# MCU_STM32F407.net
KiCad netlist of a schematic drawn in Altium Designer
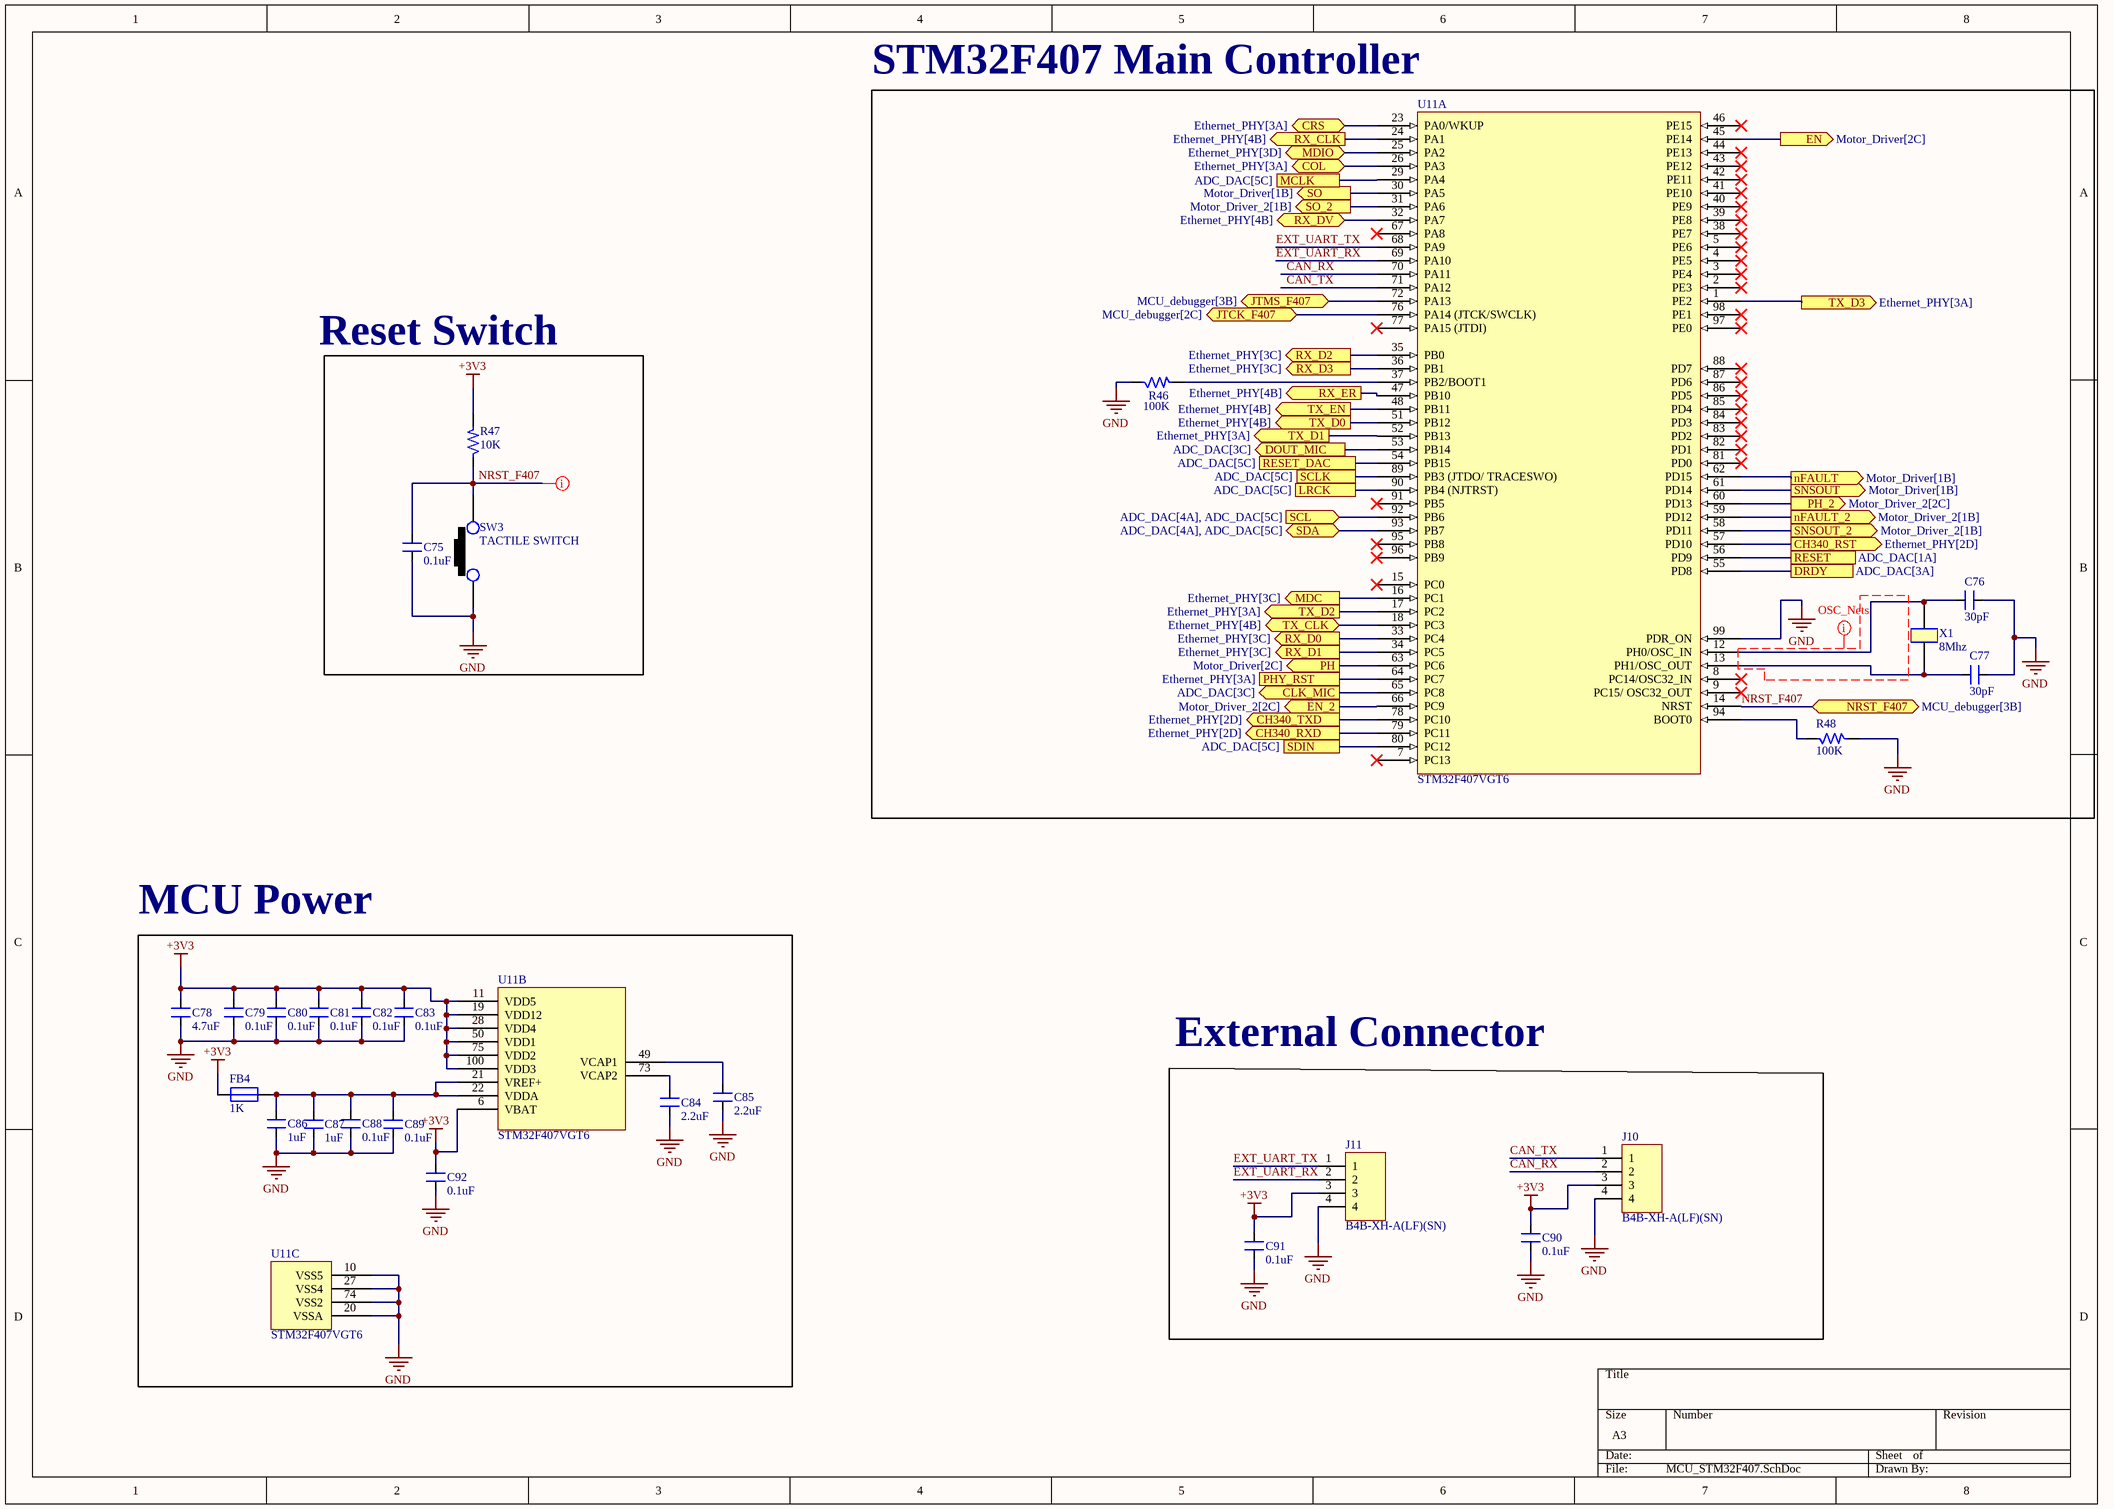
[diagram p0: MCU_STM32F407.SchDoc]

(export (version "E")
  (design (tool "Eeschema 10.0.6"))
  (components
    (comp (ref "C75")
      (value "0.1uF")
      (footprint "CAP_0805")
      (description "0.1µF ±10% 50V Ceramic Capacitor X7R 0805 (2012 Metric)")
      (fields
        (field (name "MANUFACTURER") "Samsung")
        (field (name "MANUFACTURER PART NUMBER") "CL21B104KBCNNNC")
      )
      (libsource (lib "STM32F407_Board") (part "CAP_0.1uF-50V-10%-0805"))
    )
    (comp (ref "C76")
      (value "30pF")
      (footprint "CAP_0805")
      (description "±10% 50V Ceramic Capacitor C0G, NP0 0805 (2012 Metric)")
      (fields
        (field (name "MANUFACTURER PART NUMBER") "C0805C300K5GAC7800")
        (field (name "MANUFACTURER") "KEMET")
      )
      (libsource (lib "STM32F407_Board") (part "CAP_30pF-50V-10%-0805"))
    )
    (comp (ref "C77")
      (value "30pF")
      (footprint "CAP_0805")
      (description "±10% 50V Ceramic Capacitor C0G, NP0 0805 (2012 Metric)")
      (fields
        (field (name "MANUFACTURER PART NUMBER") "C0805C300K5GAC7800")
        (field (name "MANUFACTURER") "KEMET")
      )
      (libsource (lib "STM32F407_Board") (part "CAP_30pF-50V-10%-0805"))
    )
    (comp (ref "C78")
      (value "4.7uF")
      (footprint "CAP_0805")
      (description "4.7µF ±10% 50V Ceramic Capacitor X5R 0805 (2012 Metric)")
      (fields
        (field (name "MANUFACTURER") "Yageo")
        (field (name "MANUFACTURER PART NUMBER") "GRM21BR61H475KE51L")
      )
      (libsource (lib "STM32F407_Board") (part "CAP_4.7uF-50V-10%-0805"))
    )
    (comp (ref "C79")
      (value "0.1uF")
      (footprint "CAP_0805")
      (description "0.1µF ±10% 50V Ceramic Capacitor X7R 0805 (2012 Metric)")
      (fields
        (field (name "MANUFACTURER") "Samsung")
        (field (name "MANUFACTURER PART NUMBER") "CL21B104KBCNNNC")
      )
      (libsource (lib "STM32F407_Board") (part "CAP_0.1uF-50V-10%-0805"))
    )
    (comp (ref "C80")
      (value "0.1uF")
      (footprint "CAP_0805")
      (description "0.1µF ±10% 50V Ceramic Capacitor X7R 0805 (2012 Metric)")
      (fields
        (field (name "MANUFACTURER") "Samsung")
        (field (name "MANUFACTURER PART NUMBER") "CL21B104KBCNNNC")
      )
      (libsource (lib "STM32F407_Board") (part "CAP_0.1uF-50V-10%-0805"))
    )
    (comp (ref "C81")
      (value "0.1uF")
      (footprint "CAP_0805")
      (description "0.1µF ±10% 50V Ceramic Capacitor X7R 0805 (2012 Metric)")
      (fields
        (field (name "MANUFACTURER") "Samsung")
        (field (name "MANUFACTURER PART NUMBER") "CL21B104KBCNNNC")
      )
      (libsource (lib "STM32F407_Board") (part "CAP_0.1uF-50V-10%-0805"))
    )
    (comp (ref "C82")
      (value "0.1uF")
      (footprint "CAP_0805")
      (description "0.1µF ±10% 50V Ceramic Capacitor X7R 0805 (2012 Metric)")
      (fields
        (field (name "MANUFACTURER") "Samsung")
        (field (name "MANUFACTURER PART NUMBER") "CL21B104KBCNNNC")
      )
      (libsource (lib "STM32F407_Board") (part "CAP_0.1uF-50V-10%-0805"))
    )
    (comp (ref "C83")
      (value "0.1uF")
      (footprint "CAP_0805")
      (description "0.1µF ±10% 50V Ceramic Capacitor X7R 0805 (2012 Metric)")
      (fields
        (field (name "MANUFACTURER") "Samsung")
        (field (name "MANUFACTURER PART NUMBER") "CL21B104KBCNNNC")
      )
      (libsource (lib "STM32F407_Board") (part "CAP_0.1uF-50V-10%-0805"))
    )
    (comp (ref "C84")
      (value "2.2uF")
      (footprint "CAP_0805")
      (description "2.2µF ±10% 25V Ceramic Capacitor X7R 0805 (2012 Metric)")
      (fields
        (field (name "MANUFACTURER") "KEMET")
        (field (name "MANUFACTURER PART NUMBER") "CL21B225KAFNFNE")
      )
      (libsource (lib "STM32F407_Board") (part "CAP_2.2uF-25V-10%-0805"))
    )
    (comp (ref "C85")
      (value "2.2uF")
      (footprint "CAP_0805")
      (description "2.2µF ±10% 25V Ceramic Capacitor X7R 0805 (2012 Metric)")
      (fields
        (field (name "MANUFACTURER") "KEMET")
        (field (name "MANUFACTURER PART NUMBER") "CL21B225KAFNFNE")
      )
      (libsource (lib "STM32F407_Board") (part "CAP_2.2uF-25V-10%-0805"))
    )
    (comp (ref "C86")
      (value "1uF")
      (footprint "CAP_0805")
      (description "1µF ±5% 50V Ceramic Capacitor X7R 0805 (2012 Metric)")
      (fields
        (field (name "MANUFACTURER") "Samsung")
        (field (name "MANUFACTURER PART NUMBER") "CC0805JKX7R9BB105")
      )
      (libsource (lib "STM32F407_Board") (part "CAP_1uF-50V-5%-0805"))
    )
    (comp (ref "C87")
      (value "1uF")
      (footprint "CAP_0805")
      (description "1µF ±5% 50V Ceramic Capacitor X7R 0805 (2012 Metric)")
      (fields
        (field (name "MANUFACTURER") "Samsung")
        (field (name "MANUFACTURER PART NUMBER") "CC0805JKX7R9BB105")
      )
      (libsource (lib "STM32F407_Board") (part "CAP_1uF-50V-5%-0805"))
    )
    (comp (ref "C88")
      (value "0.1uF")
      (footprint "CAP_0805")
      (description "0.1µF ±10% 50V Ceramic Capacitor X7R 0805 (2012 Metric)")
      (fields
        (field (name "MANUFACTURER") "Samsung")
        (field (name "MANUFACTURER PART NUMBER") "CL21B104KBCNNNC")
      )
      (libsource (lib "STM32F407_Board") (part "CAP_0.1uF-50V-10%-0805"))
    )
    (comp (ref "C89")
      (value "0.1uF")
      (footprint "CAP_0805")
      (description "0.1µF ±10% 50V Ceramic Capacitor X7R 0805 (2012 Metric)")
      (fields
        (field (name "MANUFACTURER") "Samsung")
        (field (name "MANUFACTURER PART NUMBER") "CL21B104KBCNNNC")
      )
      (libsource (lib "STM32F407_Board") (part "CAP_0.1uF-50V-10%-0805"))
    )
    (comp (ref "C90")
      (value "0.1uF")
      (footprint "CAP_0805")
      (description "0.1µF ±10% 50V Ceramic Capacitor X7R 0805 (2012 Metric)")
      (fields
        (field (name "MANUFACTURER") "Samsung")
        (field (name "MANUFACTURER PART NUMBER") "CL21B104KBCNNNC")
      )
      (libsource (lib "STM32F407_Board") (part "CAP_0.1uF-50V-10%-0805"))
    )
    (comp (ref "C91")
      (value "0.1uF")
      (footprint "CAP_0805")
      (description "0.1µF ±10% 50V Ceramic Capacitor X7R 0805 (2012 Metric)")
      (fields
        (field (name "MANUFACTURER") "Samsung")
        (field (name "MANUFACTURER PART NUMBER") "CL21B104KBCNNNC")
      )
      (libsource (lib "STM32F407_Board") (part "CAP_0.1uF-50V-10%-0805"))
    )
    (comp (ref "C92")
      (value "0.1uF")
      (footprint "CAP_0805")
      (description "0.1µF ±10% 50V Ceramic Capacitor X7R 0805 (2012 Metric)")
      (fields
        (field (name "MANUFACTURER") "Samsung")
        (field (name "MANUFACTURER PART NUMBER") "CL21B104KBCNNNC")
      )
      (libsource (lib "STM32F407_Board") (part "CAP_0.1uF-50V-10%-0805"))
    )
    (comp (ref "FB4")
      (value "1K")
      (footprint "IND_0805")
      (description "1 kOhms @ 100MHz 1 Power Line Ferrite Bead 0805 (2012 Metric) 1.6A")
      (fields
        (field (name "MANUFACTURER") "Laird")
        (field (name "MANUFACTURER PART NUMBER") "BLM21SP102SH1D")
      )
      (libsource (lib "STM32F407_Board") (part "FB_1K-100MHZ-1.6A-0805"))
    )
    (comp (ref "J10")
      (value "B4B-XH-A(LF)(SN)")
      (footprint "CON4_100_B4B-XH-A_TH_ST")
      (description "4 Pins, 1 Row 2.54mm Pitch, straight Connector, male")
      (fields (field (name "MANUFACTURER") "Wurth Electronics") (field (name "MATING PART NUMBER") "XHP-4"))
      (libsource (lib "STM32F407_Board") (part "CON-PLG_4X1-100-ST-TH"))
    )
    (comp (ref "J11")
      (value "B4B-XH-A(LF)(SN)")
      (footprint "CON4_100_B4B-XH-A_TH_ST")
      (description "4 Pins, 1 Row 2.54mm Pitch, straight Connector, male")
      (fields (field (name "MANUFACTURER") "Wurth Electronics") (field (name "MATING PART NUMBER") "XHP-4"))
      (libsource (lib "STM32F407_Board") (part "CON-PLG_4X1-100-ST-TH"))
    )
    (comp (ref "R46")
      (value "100K")
      (footprint "RES_0603")
      (description "100 kOhms ±1% 0.1W, 1/10W Chip Resistor 0603 (1608 Metric) Automotive AEC-Q200 Thick Film")
      (fields
        (field (name "MANUFACTURER") "Stackpole Electronics")
        (field (name "MANUFACTURER PART NUMBER") "RMCF0603FT100K")
      )
      (libsource (lib "STM32F407_Board") (part "RES_100K-0.1W-1%-0603"))
    )
    (comp (ref "R47")
      (value "10K")
      (footprint "RES_0603")
      (description "10 kOhms ±1% 0.1W, 1/10W Chip Resistor 0603 (1608 Metric) Automotive AEC-Q200 Thick Film")
      (fields (field (name "MANUFACTURER") "Walsin") (field (name "MANUFACTURER PART NUMBER") "WR06X1002FTL"))
      (libsource (lib "STM32F407_Board") (part "RES_10K-0.1W-1%-0603"))
    )
    (comp (ref "R48")
      (value "100K")
      (footprint "RES_0603")
      (description "100 kOhms ±1% 0.1W, 1/10W Chip Resistor 0603 (1608 Metric) Automotive AEC-Q200 Thick Film")
      (fields
        (field (name "MANUFACTURER") "Stackpole Electronics")
        (field (name "MANUFACTURER PART NUMBER") "RMCF0603FT100K")
      )
      (libsource (lib "STM32F407_Board") (part "RES_100K-0.1W-1%-0603"))
    )
    (comp (ref "SW3")
      (value "TACTILE SWITCH")
      (footprint "SW_342_SMD")
      (description "Tactile Switch SPST-NO Top Actuated Surface Mount")
      (fields
        (field (name "MANUFACTURER") "ITT C&K")
        (field (name "MANUFACTURER PART NUMBER") "RS-282G05A3-SMRT")
      )
      (libsource (lib "STM32F407_Board") (part "SW1_RS-282G05A3-SMRT-SMD"))
    )
    (comp (ref "U11")
      (value "STM32F407VGT6")
      (footprint "QFN100_19.6_669_58X10_SMD")
      (description "ARM® Cortex®-M4 STM32F4 Microcontroller IC 32-Bit 168MHz 1MB (1M x 8) FLASH 100-LQFP (14x14)")
      (fields (field (name "MANUFACTURER") "STMicroelectronics"))
      (libsource (lib "STM32F407_Board") (part "IC_STM32F407VGT6"))
    )
    (comp (ref "X1")
      (value "8Mhz")
      (footprint "XTAL_314_240X47_SMD")
      (description "8MHz ±30ppm Crystal 32pF 60 Ohms HC-49/US")
      (fields
        (field (name "MANUFACTURER") "Fox Electronics")
        (field (name "MANUFACTURER PART NUMBER") "ECS-80-32-5PX-TR")
      )
      (libsource (lib "STM32F407_Board") (part "XTAL_8MHZ-ECS-80-32-5PX-SMD"))
    )
  )
  (nets
    (net (code "1") (name "+3V3") (class "Default")
      (node (ref "C78") (pin "2") (pinfunction "2_2") (pintype "passive"))
      (node (ref "C79") (pin "2") (pinfunction "2_2") (pintype "passive"))
      (node (ref "C80") (pin "2") (pinfunction "2_2") (pintype "passive"))
      (node (ref "C81") (pin "2") (pinfunction "2_2") (pintype "passive"))
      (node (ref "C82") (pin "2") (pinfunction "2_2") (pintype "passive"))
      (node (ref "C83") (pin "2") (pinfunction "2_2") (pintype "passive"))
      (node (ref "C90") (pin "2") (pinfunction "2_2") (pintype "passive"))
      (node (ref "C91") (pin "2") (pinfunction "2_2") (pintype "passive"))
      (node (ref "C92") (pin "2") (pinfunction "2_2") (pintype "passive"))
      (node (ref "FB4") (pin "1") (pinfunction "1_1") (pintype "passive"))
      (node (ref "J10") (pin "3") (pinfunction "3_3") (pintype "passive"))
      (node (ref "J11") (pin "3") (pinfunction "3_3") (pintype "passive"))
      (node (ref "R47") (pin "2") (pinfunction "2_2") (pintype "passive"))
      (node (ref "U11") (pin "100") (pinfunction "VDD3_100") (pintype "passive"))
      (node (ref "U11") (pin "11") (pinfunction "VDD5_11") (pintype "passive"))
      (node (ref "U11") (pin "19") (pinfunction "VDD12_19") (pintype "passive"))
      (node (ref "U11") (pin "28") (pinfunction "VDD4_28") (pintype "passive"))
      (node (ref "U11") (pin "50") (pinfunction "VDD1_50") (pintype "passive"))
      (node (ref "U11") (pin "6") (pinfunction "VBAT_6") (pintype "passive"))
      (node (ref "U11") (pin "75") (pinfunction "VDD2_75") (pintype "passive"))
    )
    (net (code "2") (name "/CAN_RX") (class "Default")
      (node (ref "J10") (pin "2") (pinfunction "2_2") (pintype "passive"))
      (node (ref "U11") (pin "70") (pinfunction "PA11_70") (pintype "input"))
    )
    (net (code "3") (name "/CAN_TX") (class "Default")
      (node (ref "J10") (pin "1") (pinfunction "1_1") (pintype "passive"))
      (node (ref "U11") (pin "71") (pinfunction "PA12_71") (pintype "input"))
    )
    (net (code "4") (name "/CH340_RST") (class "Default")
      (node (ref "U11") (pin "57") (pinfunction "PD10_57") (pintype "input"))
    )
    (net (code "5") (name "/CH340_RXD") (class "Default")
      (node (ref "U11") (pin "79") (pinfunction "PC11_79") (pintype "input"))
    )
    (net (code "6") (name "/CH340_TXD") (class "Default")
      (node (ref "U11") (pin "78") (pinfunction "PC10_78") (pintype "input"))
    )
    (net (code "7") (name "/CLK_MIC") (class "Default")
      (node (ref "U11") (pin "65") (pinfunction "PC8_65") (pintype "input"))
    )
    (net (code "8") (name "/COL") (class "Default")
      (node (ref "U11") (pin "26") (pinfunction "PA3_26") (pintype "input"))
    )
    (net (code "9") (name "/CRS") (class "Default")
      (node (ref "U11") (pin "23") (pinfunction "PA0/WKUP_23") (pintype "input"))
    )
    (net (code "10") (name "/DOUT_MIC") (class "Default")
      (node (ref "U11") (pin "53") (pinfunction "PB14_53") (pintype "input"))
    )
    (net (code "11") (name "/DRDY") (class "Default")
      (node (ref "U11") (pin "55") (pinfunction "PD8_55") (pintype "input"))
    )
    (net (code "12") (name "/EN") (class "Default")
      (node (ref "U11") (pin "45") (pinfunction "PE14_45") (pintype "input"))
    )
    (net (code "13") (name "/EN_2") (class "Default")
      (node (ref "U11") (pin "66") (pinfunction "PC9_66") (pintype "input"))
    )
    (net (code "14") (name "/EXT_UART_RX") (class "Default")
      (node (ref "J11") (pin "2") (pinfunction "2_2") (pintype "passive"))
      (node (ref "U11") (pin "69") (pinfunction "PA10_69") (pintype "input"))
    )
    (net (code "15") (name "/EXT_UART_TX") (class "Default")
      (node (ref "J11") (pin "1") (pinfunction "1_1") (pintype "passive"))
      (node (ref "U11") (pin "68") (pinfunction "PA9_68") (pintype "input"))
    )
    (net (code "16") (name "/JTCK_F407") (class "Default")
      (node (ref "U11") (pin "76") (pinfunction "PA14_(JTCK/SWCLK)_76") (pintype "input"))
    )
    (net (code "17") (name "/JTMS_F407") (class "Default")
      (node (ref "U11") (pin "72") (pinfunction "PA13_72") (pintype "input"))
    )
    (net (code "18") (name "/LRCK") (class "Default")
      (node (ref "U11") (pin "90") (pinfunction "PB4_(NJTRST)_90") (pintype "input"))
    )
    (net (code "19") (name "/MCLK") (class "Default")
      (node (ref "U11") (pin "29") (pinfunction "PA4_29") (pintype "input"))
    )
    (net (code "20") (name "/MDC") (class "Default")
      (node (ref "U11") (pin "16") (pinfunction "PC1_16") (pintype "input"))
    )
    (net (code "21") (name "/MDIO") (class "Default")
      (node (ref "U11") (pin "25") (pinfunction "PA2_25") (pintype "input"))
    )
    (net (code "22") (name "/NRST_F407") (class "Default")
      (node (ref "C75") (pin "2") (pinfunction "2_2") (pintype "passive"))
      (node (ref "R47") (pin "1") (pinfunction "1_1") (pintype "passive"))
      (node (ref "SW3") (pin "2") (pinfunction "2_2") (pintype "passive"))
      (node (ref "U11") (pin "14") (pinfunction "NRST_14") (pintype "input"))
    )
    (net (code "23") (name "/PH") (class "Default")
      (node (ref "U11") (pin "63") (pinfunction "PC6_63") (pintype "input"))
    )
    (net (code "24") (name "/PHY_RST") (class "Default")
      (node (ref "U11") (pin "64") (pinfunction "PC7_64") (pintype "input"))
    )
    (net (code "25") (name "/PH_2") (class "Default")
      (node (ref "U11") (pin "60") (pinfunction "PD13_60") (pintype "input"))
    )
    (net (code "26") (name "/RESET") (class "Default")
      (node (ref "U11") (pin "56") (pinfunction "PD9_56") (pintype "input"))
    )
    (net (code "27") (name "/RESET_DAC") (class "Default")
      (node (ref "U11") (pin "54") (pinfunction "PB15_54") (pintype "input"))
    )
    (net (code "28") (name "/RX_CLK") (class "Default")
      (node (ref "U11") (pin "24") (pinfunction "PA1_24") (pintype "input"))
    )
    (net (code "29") (name "/RX_D0") (class "Default")
      (node (ref "U11") (pin "33") (pinfunction "PC4_33") (pintype "input"))
    )
    (net (code "30") (name "/RX_D1") (class "Default")
      (node (ref "U11") (pin "34") (pinfunction "PC5_34") (pintype "input"))
    )
    (net (code "31") (name "/RX_D2") (class "Default")
      (node (ref "U11") (pin "35") (pinfunction "PB0_35") (pintype "input"))
    )
    (net (code "32") (name "/RX_D3") (class "Default")
      (node (ref "U11") (pin "36") (pinfunction "PB1_36") (pintype "input"))
    )
    (net (code "33") (name "/RX_DV") (class "Default")
      (node (ref "U11") (pin "32") (pinfunction "PA7_32") (pintype "input"))
    )
    (net (code "34") (name "/RX_ER") (class "Default")
      (node (ref "U11") (pin "47") (pinfunction "PB10_47") (pintype "input"))
    )
    (net (code "35") (name "/SCL") (class "Default")
      (node (ref "U11") (pin "92") (pinfunction "PB6_92") (pintype "input"))
    )
    (net (code "36") (name "/SCLK") (class "Default")
      (node (ref "U11") (pin "89") (pinfunction "PB3_(JTDO/_TRACESWO)_89") (pintype "input"))
    )
    (net (code "37") (name "/SDA") (class "Default")
      (node (ref "U11") (pin "93") (pinfunction "PB7_93") (pintype "input"))
    )
    (net (code "38") (name "/SDIN") (class "Default")
      (node (ref "U11") (pin "80") (pinfunction "PC12_80") (pintype "input"))
    )
    (net (code "39") (name "/SNSOUT") (class "Default")
      (node (ref "U11") (pin "61") (pinfunction "PD14_61") (pintype "input"))
    )
    (net (code "40") (name "/SNSOUT_2") (class "Default")
      (node (ref "U11") (pin "58") (pinfunction "PD11_58") (pintype "input"))
    )
    (net (code "41") (name "/SO") (class "Default")
      (node (ref "U11") (pin "30") (pinfunction "PA5_30") (pintype "input"))
    )
    (net (code "42") (name "/SO_2") (class "Default")
      (node (ref "U11") (pin "31") (pinfunction "PA6_31") (pintype "input"))
    )
    (net (code "43") (name "/TX_CLK") (class "Default")
      (node (ref "U11") (pin "18") (pinfunction "PC3_18") (pintype "input"))
    )
    (net (code "44") (name "/TX_D0") (class "Default")
      (node (ref "U11") (pin "51") (pinfunction "PB12_51") (pintype "input"))
    )
    (net (code "45") (name "/TX_D1") (class "Default")
      (node (ref "U11") (pin "52") (pinfunction "PB13_52") (pintype "input"))
    )
    (net (code "46") (name "/TX_D2") (class "Default")
      (node (ref "U11") (pin "17") (pinfunction "PC2_17") (pintype "input"))
    )
    (net (code "47") (name "/TX_D3") (class "Default")
      (node (ref "U11") (pin "1") (pinfunction "PE2_1") (pintype "input"))
    )
    (net (code "48") (name "/TX_EN") (class "Default")
      (node (ref "U11") (pin "48") (pinfunction "PB11_48") (pintype "input"))
    )
    (net (code "49") (name "/nFAULT") (class "Default")
      (node (ref "U11") (pin "62") (pinfunction "PD15_62") (pintype "input"))
    )
    (net (code "50") (name "/nFAULT_2") (class "Default")
      (node (ref "U11") (pin "59") (pinfunction "PD12_59") (pintype "input"))
    )
    (net (code "51") (name "GND") (class "Default")
      (node (ref "C75") (pin "1") (pinfunction "1_1") (pintype "passive"))
      (node (ref "C76") (pin "2") (pinfunction "2_2") (pintype "passive"))
      (node (ref "C77") (pin "2") (pinfunction "2_2") (pintype "passive"))
      (node (ref "C78") (pin "1") (pinfunction "1_1") (pintype "passive"))
      (node (ref "C79") (pin "1") (pinfunction "1_1") (pintype "passive"))
      (node (ref "C80") (pin "1") (pinfunction "1_1") (pintype "passive"))
      (node (ref "C81") (pin "1") (pinfunction "1_1") (pintype "passive"))
      (node (ref "C82") (pin "1") (pinfunction "1_1") (pintype "passive"))
      (node (ref "C83") (pin "1") (pinfunction "1_1") (pintype "passive"))
      (node (ref "C84") (pin "1") (pinfunction "1_1") (pintype "passive"))
      (node (ref "C85") (pin "1") (pinfunction "1_1") (pintype "passive"))
      (node (ref "C86") (pin "1") (pinfunction "1_1") (pintype "passive"))
      (node (ref "C87") (pin "1") (pinfunction "1_1") (pintype "passive"))
      (node (ref "C88") (pin "1") (pinfunction "1_1") (pintype "passive"))
      (node (ref "C89") (pin "1") (pinfunction "1_1") (pintype "passive"))
      (node (ref "C90") (pin "1") (pinfunction "1_1") (pintype "passive"))
      (node (ref "C91") (pin "1") (pinfunction "1_1") (pintype "passive"))
      (node (ref "C92") (pin "1") (pinfunction "1_1") (pintype "passive"))
      (node (ref "J10") (pin "4") (pinfunction "4_4") (pintype "passive"))
      (node (ref "J11") (pin "4") (pinfunction "4_4") (pintype "passive"))
      (node (ref "R46") (pin "1") (pinfunction "1_1") (pintype "passive"))
      (node (ref "R48") (pin "2") (pinfunction "2_2") (pintype "passive"))
      (node (ref "SW3") (pin "1") (pinfunction "1_1") (pintype "passive"))
      (node (ref "U11") (pin "10") (pinfunction "VSS5_10") (pintype "passive"))
      (node (ref "U11") (pin "20") (pinfunction "VSSA_20") (pintype "passive"))
      (node (ref "U11") (pin "27") (pinfunction "VSS4_27") (pintype "passive"))
      (node (ref "U11") (pin "74") (pinfunction "VSS2_74") (pintype "passive"))
      (node (ref "U11") (pin "99") (pinfunction "PDR_ON_99") (pintype "input"))
    )
    (net (code "52") (name "Net-(U11A-BOOT0)") (class "Default")
      (node (ref "R48") (pin "1") (pinfunction "1_1") (pintype "passive"))
      (node (ref "U11") (pin "94") (pinfunction "BOOT0_94") (pintype "input"))
    )
    (net (code "53") (name "Net-(U11A-PB2{slash}BOOT1)") (class "Default")
      (node (ref "R46") (pin "2") (pinfunction "2_2") (pintype "passive"))
      (node (ref "U11") (pin "37") (pinfunction "PB2/BOOT1_37") (pintype "input"))
    )
    (net (code "54") (name "Net-(U11A-PH0{slash}OSC_IN)") (class "Default")
      (node (ref "C76") (pin "1") (pinfunction "1_1") (pintype "passive"))
      (node (ref "U11") (pin "12") (pinfunction "PH0/OSC_IN_12") (pintype "input"))
      (node (ref "X1") (pin "2") (pinfunction "2_2") (pintype "passive"))
    )
    (net (code "55") (name "Net-(U11A-PH1{slash}OSC_OUT)") (class "Default")
      (node (ref "C77") (pin "1") (pinfunction "1_1") (pintype "passive"))
      (node (ref "U11") (pin "13") (pinfunction "PH1/OSC_OUT_13") (pintype "input"))
      (node (ref "X1") (pin "1") (pinfunction "1_1") (pintype "passive"))
    )
    (net (code "56") (name "Net-(U11B-VCAP1)") (class "Default")
      (node (ref "C85") (pin "2") (pinfunction "2_2") (pintype "passive"))
      (node (ref "U11") (pin "49") (pinfunction "VCAP1_49") (pintype "passive"))
    )
    (net (code "57") (name "Net-(U11B-VCAP2)") (class "Default")
      (node (ref "C84") (pin "2") (pinfunction "2_2") (pintype "passive"))
      (node (ref "U11") (pin "73") (pinfunction "VCAP2_73") (pintype "passive"))
    )
    (net (code "58") (name "Net-(U11B-VDDA)") (class "Default")
      (node (ref "C86") (pin "2") (pinfunction "2_2") (pintype "passive"))
      (node (ref "C87") (pin "2") (pinfunction "2_2") (pintype "passive"))
      (node (ref "C88") (pin "2") (pinfunction "2_2") (pintype "passive"))
      (node (ref "C89") (pin "2") (pinfunction "2_2") (pintype "passive"))
      (node (ref "FB4") (pin "2") (pinfunction "2_2") (pintype "passive"))
      (node (ref "U11") (pin "21") (pinfunction "VREF+_21") (pintype "passive"))
      (node (ref "U11") (pin "22") (pinfunction "VDDA_22") (pintype "passive"))
    )
    (net (code "59") (name "unconnected-(U11A-PA8-Pad67)") (class "Default")
      (node (ref "U11") (pin "67") (pinfunction "PA8_67") (pintype "input+no_connect"))
    )
    (net (code "60") (name "unconnected-(U11A-PA15_(JTDI)-Pad77)") (class "Default")
      (node (ref "U11") (pin "77") (pinfunction "PA15_(JTDI)_77") (pintype "input+no_connect"))
    )
    (net (code "61") (name "unconnected-(U11A-PB5-Pad91)") (class "Default")
      (node (ref "U11") (pin "91") (pinfunction "PB5_91") (pintype "input+no_connect"))
    )
    (net (code "62") (name "unconnected-(U11A-PB8-Pad95)") (class "Default")
      (node (ref "U11") (pin "95") (pinfunction "PB8_95") (pintype "input+no_connect"))
    )
    (net (code "63") (name "unconnected-(U11A-PB9-Pad96)") (class "Default")
      (node (ref "U11") (pin "96") (pinfunction "PB9_96") (pintype "input+no_connect"))
    )
    (net (code "64") (name "unconnected-(U11A-PC0-Pad15)") (class "Default")
      (node (ref "U11") (pin "15") (pinfunction "PC0_15") (pintype "input+no_connect"))
    )
    (net (code "65") (name "unconnected-(U11A-PC13-Pad7)") (class "Default")
      (node (ref "U11") (pin "7") (pinfunction "PC13_7") (pintype "input+no_connect"))
    )
    (net (code "66") (name "unconnected-(U11A-PC14{slash}OSC32_IN-Pad8)") (class "Default")
      (node (ref "U11") (pin "8") (pinfunction "PC14/OSC32_IN_8") (pintype "input+no_connect"))
    )
    (net (code "67") (name "unconnected-(U11A-PC15{slash}_OSC32_OUT-Pad9)") (class "Default")
      (node (ref "U11") (pin "9") (pinfunction "PC15/_OSC32_OUT_9") (pintype "input+no_connect"))
    )
    (net (code "68") (name "unconnected-(U11A-PD0-Pad81)") (class "Default")
      (node (ref "U11") (pin "81") (pinfunction "PD0_81") (pintype "input+no_connect"))
    )
    (net (code "69") (name "unconnected-(U11A-PD1-Pad82)") (class "Default")
      (node (ref "U11") (pin "82") (pinfunction "PD1_82") (pintype "input+no_connect"))
    )
    (net (code "70") (name "unconnected-(U11A-PD2-Pad83)") (class "Default")
      (node (ref "U11") (pin "83") (pinfunction "PD2_83") (pintype "input+no_connect"))
    )
    (net (code "71") (name "unconnected-(U11A-PD3-Pad84)") (class "Default")
      (node (ref "U11") (pin "84") (pinfunction "PD3_84") (pintype "input+no_connect"))
    )
    (net (code "72") (name "unconnected-(U11A-PD4-Pad85)") (class "Default")
      (node (ref "U11") (pin "85") (pinfunction "PD4_85") (pintype "input+no_connect"))
    )
    (net (code "73") (name "unconnected-(U11A-PD5-Pad86)") (class "Default")
      (node (ref "U11") (pin "86") (pinfunction "PD5_86") (pintype "input+no_connect"))
    )
    (net (code "74") (name "unconnected-(U11A-PD6-Pad87)") (class "Default")
      (node (ref "U11") (pin "87") (pinfunction "PD6_87") (pintype "input+no_connect"))
    )
    (net (code "75") (name "unconnected-(U11A-PD7-Pad88)") (class "Default")
      (node (ref "U11") (pin "88") (pinfunction "PD7_88") (pintype "input+no_connect"))
    )
    (net (code "76") (name "unconnected-(U11A-PE0-Pad97)") (class "Default")
      (node (ref "U11") (pin "97") (pinfunction "PE0_97") (pintype "input+no_connect"))
    )
    (net (code "77") (name "unconnected-(U11A-PE1-Pad98)") (class "Default")
      (node (ref "U11") (pin "98") (pinfunction "PE1_98") (pintype "input+no_connect"))
    )
    (net (code "78") (name "unconnected-(U11A-PE3-Pad2)") (class "Default")
      (node (ref "U11") (pin "2") (pinfunction "PE3_2") (pintype "input+no_connect"))
    )
    (net (code "79") (name "unconnected-(U11A-PE4-Pad3)") (class "Default")
      (node (ref "U11") (pin "3") (pinfunction "PE4_3") (pintype "input+no_connect"))
    )
    (net (code "80") (name "unconnected-(U11A-PE5-Pad4)") (class "Default")
      (node (ref "U11") (pin "4") (pinfunction "PE5_4") (pintype "input+no_connect"))
    )
    (net (code "81") (name "unconnected-(U11A-PE6-Pad5)") (class "Default")
      (node (ref "U11") (pin "5") (pinfunction "PE6_5") (pintype "input+no_connect"))
    )
    (net (code "82") (name "unconnected-(U11A-PE7-Pad38)") (class "Default")
      (node (ref "U11") (pin "38") (pinfunction "PE7_38") (pintype "input+no_connect"))
    )
    (net (code "83") (name "unconnected-(U11A-PE8-Pad39)") (class "Default")
      (node (ref "U11") (pin "39") (pinfunction "PE8_39") (pintype "input+no_connect"))
    )
    (net (code "84") (name "unconnected-(U11A-PE9-Pad40)") (class "Default")
      (node (ref "U11") (pin "40") (pinfunction "PE9_40") (pintype "input+no_connect"))
    )
    (net (code "85") (name "unconnected-(U11A-PE10-Pad41)") (class "Default")
      (node (ref "U11") (pin "41") (pinfunction "PE10_41") (pintype "input+no_connect"))
    )
    (net (code "86") (name "unconnected-(U11A-PE11-Pad42)") (class "Default")
      (node (ref "U11") (pin "42") (pinfunction "PE11_42") (pintype "input+no_connect"))
    )
    (net (code "87") (name "unconnected-(U11A-PE12-Pad43)") (class "Default")
      (node (ref "U11") (pin "43") (pinfunction "PE12_43") (pintype "input+no_connect"))
    )
    (net (code "88") (name "unconnected-(U11A-PE13-Pad44)") (class "Default")
      (node (ref "U11") (pin "44") (pinfunction "PE13_44") (pintype "input+no_connect"))
    )
    (net (code "89") (name "unconnected-(U11A-PE15-Pad46)") (class "Default")
      (node (ref "U11") (pin "46") (pinfunction "PE15_46") (pintype "input+no_connect"))
    )
  )
)
